# Symmetric_PS.net
KiCad netlist of a schematic drawn in Altium Designer
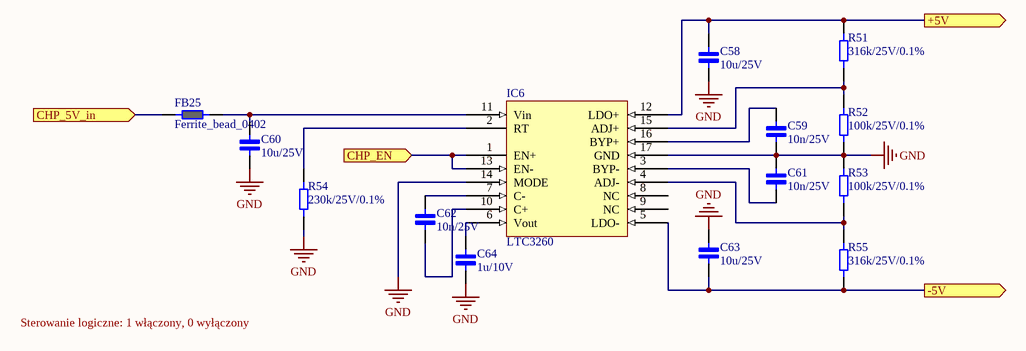
[diagram p0: Symmetric_PS.SchDoc]

(export (version "E")
  (design (tool "Eeschema 10.0.6"))
  (components
    (comp (ref "C58")
      (value "10u/25V")
      (footprint "CAP_0805")
      (description "Ceramic Capacitor 10uF / 0805 / 25V / ±5%, Wurth Elektronik MLCC")
      (libsource (lib "Cubesat_lib") (part "Cap_0805_10u_25v"))
    )
    (comp (ref "C59")
      (value "10n/25V")
      (footprint "Cap_0402")
      (description "Ceramic Capacitor 10n / 0402 / 25V / ±5%, Wurth Elektronik MLCC")
      (libsource (lib "Cubesat_lib") (part "Cap_0402_10n"))
    )
    (comp (ref "C60")
      (value "10u/25V")
      (footprint "CAP_0805")
      (description "Ceramic Capacitor 10uF / 0805 / 25V / ±5%, Wurth Elektronik MLCC")
      (libsource (lib "Cubesat_lib") (part "Cap_0805_10u_25v"))
    )
    (comp (ref "C61")
      (value "10n/25V")
      (footprint "Cap_0402")
      (description "Ceramic Capacitor 10n / 0402 / 25V / ±5%, Wurth Elektronik MLCC")
      (libsource (lib "Cubesat_lib") (part "Cap_0402_10n"))
    )
    (comp (ref "C62")
      (value "10n/25V")
      (footprint "Cap_0402")
      (description "Ceramic Capacitor 10n / 0402 / 25V / ±5%, Wurth Elektronik MLCC")
      (libsource (lib "Cubesat_lib") (part "Cap_0402_10n"))
    )
    (comp (ref "C63")
      (value "10u/25V")
      (footprint "CAP_0805")
      (description "Ceramic Capacitor 10uF / 0805 / 25V / ±5%, Wurth Elektronik MLCC")
      (libsource (lib "Cubesat_lib") (part "Cap_0805_10u_25v"))
    )
    (comp (ref "C64")
      (value "1u/10V")
      (footprint "Cap_0402")
      (description "Ceramic Capacitor 1uF / 0402 / 10V / ±5%, Wurth Elektronik MLCC")
      (libsource (lib "Cubesat_lib") (part "Cap_0402_1u"))
    )
    (comp (ref "FB25")
      (value "Ferrite_bead_0402")
      (footprint "FERRITE_0402")
      (description "Ferrite bead, wurth 74269241102")
      (libsource (lib "Cubesat_lib") (part "Ferrite_bead_0402"))
    )
    (comp (ref "IC6")
      (value "LTC3260")
      (footprint "MSOP-16")
      (description "Charge pump, low noise")
      (libsource (lib "Cubesat_lib") (part "LTC3260"))
    )
    (comp (ref "R51")
      (value "316k/25V/0.1%")
      (footprint "RES_0402")
      (description "Vishay, thin film resistor 316k/25V/0.1%")
      (libsource (lib "Cubesat_lib") (part "Res_0402_316k"))
    )
    (comp (ref "R52")
      (value "100k/25V/0.1%")
      (footprint "RES_0402")
      (description "Vishay, thin film resistor 100k/25V/0.1%")
      (libsource (lib "Cubesat_lib") (part "Res_0402_100k"))
    )
    (comp (ref "R53")
      (value "100k/25V/0.1%")
      (footprint "RES_0402")
      (description "Vishay, thin film resistor 100k/25V/0.1%")
      (libsource (lib "Cubesat_lib") (part "Res_0402_100k"))
    )
    (comp (ref "R54")
      (value "230k/25V/0.1%")
      (footprint "RES_0402")
      (description "Vishay, thin film resistor 230k/25V/0.1%")
      (libsource (lib "Cubesat_lib") (part "Res_0402_230k"))
    )
    (comp (ref "R55")
      (value "316k/25V/0.1%")
      (footprint "RES_0402")
      (description "Vishay, thin film resistor 316k/25V/0.1%")
      (libsource (lib "Cubesat_lib") (part "Res_0402_316k"))
    )
  )
  (nets
    (net (code "1") (name "/+5V") (class "Default")
      (node (ref "C58") (pin "2") (pinfunction "2_2") (pintype "passive"))
      (node (ref "IC6") (pin "12") (pinfunction "LDO+_12") (pintype "input"))
      (node (ref "R51") (pin "2") (pinfunction "2_2") (pintype "passive"))
    )
    (net (code "2") (name "/-5V") (class "Default")
      (node (ref "C63") (pin "1") (pinfunction "1_1") (pintype "passive"))
      (node (ref "IC6") (pin "5") (pinfunction "LDO-_5") (pintype "input"))
      (node (ref "R55") (pin "1") (pinfunction "1_1") (pintype "passive"))
    )
    (net (code "3") (name "/CHP_5V_in") (class "Default")
      (node (ref "FB25") (pin "1") (pinfunction "1_1") (pintype "passive"))
    )
    (net (code "4") (name "/CHP_EN") (class "Default")
      (node (ref "IC6") (pin "1") (pinfunction "EN+_1") (pintype "passive"))
      (node (ref "IC6") (pin "13") (pinfunction "EN-_13") (pintype "input"))
    )
    (net (code "5") (name "GND") (class "Default")
      (node (ref "C58") (pin "1") (pinfunction "1_1") (pintype "passive"))
      (node (ref "C59") (pin "1") (pinfunction "1_1") (pintype "passive"))
      (node (ref "C60") (pin "1") (pinfunction "1_1") (pintype "passive"))
      (node (ref "C61") (pin "2") (pinfunction "2_2") (pintype "passive"))
      (node (ref "C63") (pin "2") (pinfunction "2_2") (pintype "passive"))
      (node (ref "C64") (pin "1") (pinfunction "1_1") (pintype "passive"))
      (node (ref "IC6") (pin "14") (pinfunction "MODE_14") (pintype "input"))
      (node (ref "IC6") (pin "17") (pinfunction "GND_17") (pintype "input"))
      (node (ref "R52") (pin "1") (pinfunction "1_1") (pintype "passive"))
      (node (ref "R53") (pin "2") (pinfunction "2_2") (pintype "passive"))
      (node (ref "R54") (pin "1") (pinfunction "1_1") (pintype "passive"))
    )
    (net (code "6") (name "Net-(IC6-ADJ+)") (class "Default")
      (node (ref "IC6") (pin "15") (pinfunction "ADJ+_15") (pintype "input"))
      (node (ref "R51") (pin "1") (pinfunction "1_1") (pintype "passive"))
      (node (ref "R52") (pin "2") (pinfunction "2_2") (pintype "passive"))
    )
    (net (code "7") (name "Net-(IC6-ADJ-)") (class "Default")
      (node (ref "IC6") (pin "4") (pinfunction "ADJ-_4") (pintype "input"))
      (node (ref "R53") (pin "1") (pinfunction "1_1") (pintype "passive"))
      (node (ref "R55") (pin "2") (pinfunction "2_2") (pintype "passive"))
    )
    (net (code "8") (name "Net-(IC6-BYP+)") (class "Default")
      (node (ref "C59") (pin "2") (pinfunction "2_2") (pintype "passive"))
      (node (ref "IC6") (pin "16") (pinfunction "BYP+_16") (pintype "input"))
    )
    (net (code "9") (name "Net-(IC6-BYP-)") (class "Default")
      (node (ref "C61") (pin "1") (pinfunction "1_1") (pintype "passive"))
      (node (ref "IC6") (pin "3") (pinfunction "BYP-_3") (pintype "input"))
    )
    (net (code "10") (name "Net-(IC6-C+)") (class "Default")
      (node (ref "C62") (pin "1") (pinfunction "1_1") (pintype "passive"))
      (node (ref "IC6") (pin "10") (pinfunction "C+_10") (pintype "input"))
    )
    (net (code "11") (name "Net-(IC6-C-)") (class "Default")
      (node (ref "C62") (pin "2") (pinfunction "2_2") (pintype "passive"))
      (node (ref "IC6") (pin "7") (pinfunction "C-_7") (pintype "input"))
    )
    (net (code "12") (name "Net-(IC6-RT)") (class "Default")
      (node (ref "IC6") (pin "2") (pinfunction "RT_2") (pintype "passive"))
      (node (ref "R54") (pin "2") (pinfunction "2_2") (pintype "passive"))
    )
    (net (code "13") (name "Net-(IC6-Vin)") (class "Default")
      (node (ref "C60") (pin "2") (pinfunction "2_2") (pintype "passive"))
      (node (ref "FB25") (pin "2") (pinfunction "2_2") (pintype "passive"))
      (node (ref "IC6") (pin "11") (pinfunction "Vin_11") (pintype "input"))
    )
    (net (code "14") (name "Net-(IC6-Vout)") (class "Default")
      (node (ref "C64") (pin "2") (pinfunction "2_2") (pintype "passive"))
      (node (ref "IC6") (pin "6") (pinfunction "Vout_6") (pintype "input"))
    )
    (net (code "15") (name "unconnected-(IC6-NC-Pad8)") (class "Default")
      (node (ref "IC6") (pin "8") (pinfunction "NC_8") (pintype "input"))
    )
    (net (code "16") (name "unconnected-(IC6-NC-Pad9)") (class "Default")
      (node (ref "IC6") (pin "9") (pinfunction "NC_9") (pintype "input"))
    )
  )
)
